# SCH_555-circuit_2025-12-22.net
KiCad netlist of a schematic drawn in EasyEDA
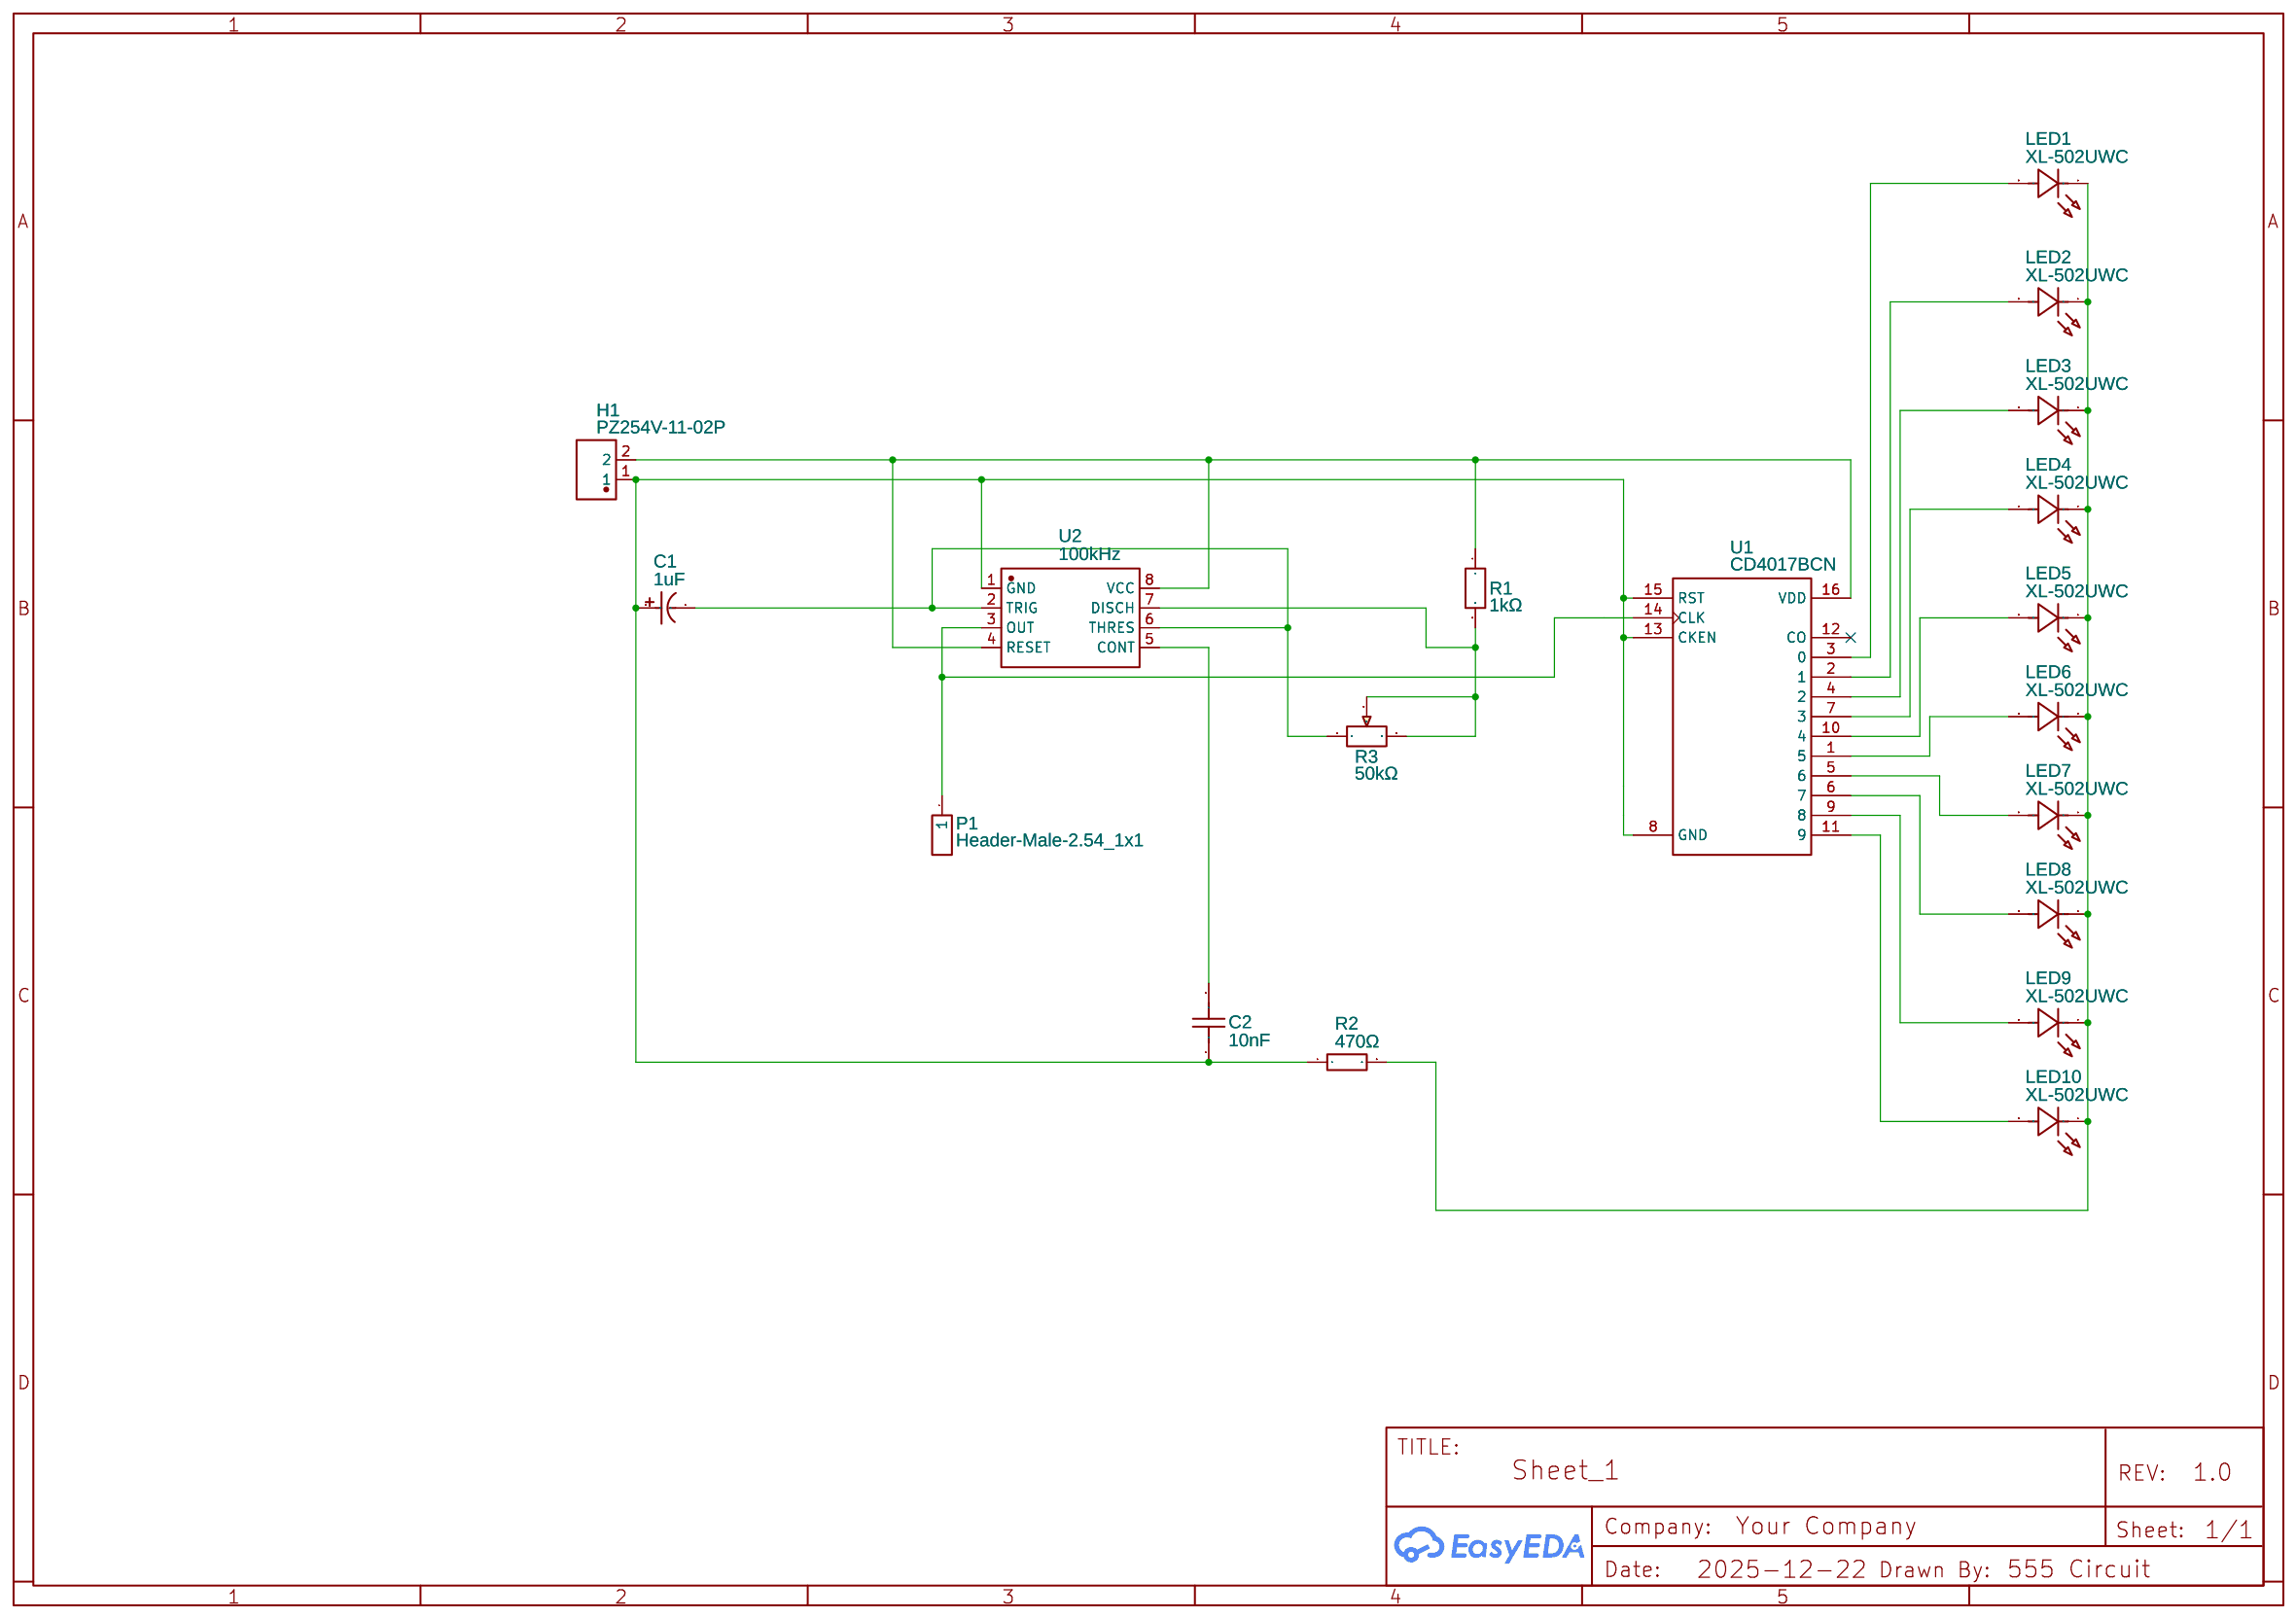
[diagram p0: schematic sheet]

(export (version "E")
  (design (tool "Eeschema 10.0.6"))
  (components
    (comp (ref "C1")
      (value "1uF")
      (fields (field (name "Manufacturer Part") "KF010M050C110A") (field (name "Manufacturer") "CapXon(丰宾)"))
      (libsource (lib "") (part "KF010M050C110A"))
    )
    (comp (ref "C2")
      (value "10nF")
      (fields (field (name "Manufacturer Part") "N09F1B103MN0B0S0N0") (field (name "Manufacturer") "STE(松田)"))
      (libsource (lib "") (part "N09F1B103MN0B0S0N0"))
    )
    (comp (ref "H1")
      (value "PZ254V-11-02P")
      (fields (field (name "Manufacturer") "XFCN(兴飞)"))
      (libsource (lib "") (part "PZ254V-11-02P"))
    )
    (comp (ref "LED1")
      (value "XL-502UWC")
      (fields (field (name "Manufacturer") "XINGLIGHT(成兴光)"))
      (libsource (lib "") (part "XL-502UWC"))
    )
    (comp (ref "LED2")
      (value "XL-502UWC")
      (fields (field (name "Manufacturer") "XINGLIGHT(成兴光)"))
      (libsource (lib "") (part "XL-502UWC"))
    )
    (comp (ref "LED3")
      (value "XL-502UWC")
      (fields (field (name "Manufacturer") "XINGLIGHT(成兴光)"))
      (libsource (lib "") (part "XL-502UWC"))
    )
    (comp (ref "LED4")
      (value "XL-502UWC")
      (fields (field (name "Manufacturer") "XINGLIGHT(成兴光)"))
      (libsource (lib "") (part "XL-502UWC"))
    )
    (comp (ref "LED5")
      (value "XL-502UWC")
      (fields (field (name "Manufacturer") "XINGLIGHT(成兴光)"))
      (libsource (lib "") (part "XL-502UWC"))
    )
    (comp (ref "LED6")
      (value "XL-502UWC")
      (fields (field (name "Manufacturer") "XINGLIGHT(成兴光)"))
      (libsource (lib "") (part "XL-502UWC"))
    )
    (comp (ref "LED7")
      (value "XL-502UWC")
      (fields (field (name "Manufacturer") "XINGLIGHT(成兴光)"))
      (libsource (lib "") (part "XL-502UWC"))
    )
    (comp (ref "LED8")
      (value "XL-502UWC")
      (fields (field (name "Manufacturer") "XINGLIGHT(成兴光)"))
      (libsource (lib "") (part "XL-502UWC"))
    )
    (comp (ref "LED9")
      (value "XL-502UWC")
      (fields (field (name "Manufacturer") "XINGLIGHT(成兴光)"))
      (libsource (lib "") (part "XL-502UWC"))
    )
    (comp (ref "LED10")
      (value "XL-502UWC")
      (fields (field (name "Manufacturer") "XINGLIGHT(成兴光)"))
      (libsource (lib "") (part "XL-502UWC"))
    )
    (comp (ref "P1")
      (value "Header-Male-2.54_1x1")
      (fields (field (name "Manufacturer Part") "2.54-1*1P针") (field (name "Manufacturer") "BOOMELE(博穆精密)"))
      (libsource (lib "") (part "Header-Male-2.54_1x1"))
    )
    (comp (ref "R1")
      (value "1kΩ")
      (fields (field (name "Manufacturer Part") "MF1/4W-1KΩ±1%T52") (field (name "Manufacturer") "华星机电"))
      (libsource (lib "") (part "MF1/4W-1KΩ±1%T52"))
    )
    (comp (ref "R2")
      (value "470Ω")
      (fields
        (field (name "Manufacturer Part") "MFR0W4F4700A50")
        (field (name "Manufacturer") "UNI-ROYAL(厚声)")
      )
      (libsource (lib "") (part "MFR0W4F4700A50"))
    )
    (comp (ref "R3")
      (value "50kΩ")
      (fields (field (name "Manufacturer Part") "3296X-1-503") (field (name "Manufacturer") "BOCHEN(博晨)"))
      (libsource (lib "") (part "3296X-1-503_C118912"))
    )
    (comp (ref "U1") (value "CD4017BCN") (libsource (lib "") (part "CD4017BCN")))
    (comp (ref "U2")
      (value "100kHz")
      (fields (field (name "Manufacturer Part") "NE555P") (field (name "Manufacturer") "TI(德州仪器)"))
      (libsource (lib "") (part "NE555P"))
    )
  )
  (nets
    (net (code "1") (name "Net-(LED1-A)") (class "Default")
      (node (ref "LED1") (pin "2") (pinfunction "A_2") (pintype "unspecified"))
      (node (ref "U1") (pin "3") (pinfunction "0_3") (pintype "output"))
    )
    (net (code "2") (name "Net-(LED1-K)") (class "Default")
      (node (ref "LED1") (pin "1") (pinfunction "K_1") (pintype "unspecified"))
      (node (ref "LED10") (pin "1") (pinfunction "K_1") (pintype "unspecified"))
      (node (ref "LED2") (pin "1") (pinfunction "K_1") (pintype "unspecified"))
      (node (ref "LED3") (pin "1") (pinfunction "K_1") (pintype "unspecified"))
      (node (ref "LED4") (pin "1") (pinfunction "K_1") (pintype "unspecified"))
      (node (ref "LED5") (pin "1") (pinfunction "K_1") (pintype "unspecified"))
      (node (ref "LED6") (pin "1") (pinfunction "K_1") (pintype "unspecified"))
      (node (ref "LED7") (pin "1") (pinfunction "K_1") (pintype "unspecified"))
      (node (ref "LED8") (pin "1") (pinfunction "K_1") (pintype "unspecified"))
      (node (ref "LED9") (pin "1") (pinfunction "K_1") (pintype "unspecified"))
      (node (ref "R2") (pin "2") (pinfunction "2_2") (pintype "input"))
    )
    (net (code "3") (name "Net-(LED2-A)") (class "Default")
      (node (ref "LED2") (pin "2") (pinfunction "A_2") (pintype "unspecified"))
      (node (ref "U1") (pin "2") (pinfunction "1_2") (pintype "output"))
    )
    (net (code "4") (name "Net-(LED3-A)") (class "Default")
      (node (ref "LED3") (pin "2") (pinfunction "A_2") (pintype "unspecified"))
      (node (ref "U1") (pin "4") (pinfunction "2_4") (pintype "output"))
    )
    (net (code "5") (name "Net-(LED4-A)") (class "Default")
      (node (ref "LED4") (pin "2") (pinfunction "A_2") (pintype "unspecified"))
      (node (ref "U1") (pin "7") (pinfunction "3_7") (pintype "output"))
    )
    (net (code "6") (name "Net-(LED5-A)") (class "Default")
      (node (ref "LED5") (pin "2") (pinfunction "A_2") (pintype "unspecified"))
      (node (ref "U1") (pin "10") (pinfunction "4_10") (pintype "output"))
    )
    (net (code "7") (name "Net-(LED6-A)") (class "Default")
      (node (ref "LED6") (pin "2") (pinfunction "A_2") (pintype "unspecified"))
      (node (ref "U1") (pin "1") (pinfunction "5_1") (pintype "output"))
    )
    (net (code "8") (name "Net-(LED7-A)") (class "Default")
      (node (ref "LED7") (pin "2") (pinfunction "A_2") (pintype "unspecified"))
      (node (ref "U1") (pin "5") (pinfunction "6_5") (pintype "output"))
    )
    (net (code "9") (name "Net-(LED8-A)") (class "Default")
      (node (ref "LED8") (pin "2") (pinfunction "A_2") (pintype "unspecified"))
      (node (ref "U1") (pin "6") (pinfunction "7_6") (pintype "output"))
    )
    (net (code "10") (name "Net-(LED9-A)") (class "Default")
      (node (ref "LED9") (pin "2") (pinfunction "A_2") (pintype "unspecified"))
      (node (ref "U1") (pin "9") (pinfunction "8_9") (pintype "output"))
    )
    (net (code "11") (name "Net-(LED10-A)") (class "Default")
      (node (ref "LED10") (pin "2") (pinfunction "A_2") (pintype "unspecified"))
      (node (ref "U1") (pin "11") (pinfunction "9_11") (pintype "output"))
    )
    (net (code "12") (name "Net-(U1-CKEN)") (class "Default")
      (node (ref "C1") (pin "1") (pinfunction "1_1") (pintype "input"))
      (node (ref "C2") (pin "1") (pinfunction "1_1") (pintype "unspecified"))
      (node (ref "H1") (pin "1") (pinfunction "1_1") (pintype "unspecified"))
      (node (ref "R2") (pin "1") (pinfunction "1_1") (pintype "input"))
      (node (ref "U1") (pin "13") (pinfunction "CKEN_13") (pintype "unspecified"))
      (node (ref "U1") (pin "15") (pinfunction "RST_15") (pintype "unspecified"))
      (node (ref "U1") (pin "8") (pinfunction "GND_8") (pintype "passive"))
      (node (ref "U2") (pin "1") (pinfunction "GND_1") (pintype "unspecified"))
    )
    (net (code "13") (name "Net-(U1-CLK)") (class "Default")
      (node (ref "P1") (pin "1") (pinfunction "1_1") (pintype "input"))
      (node (ref "U1") (pin "14") (pinfunction "CLK_14") (pintype "unspecified"))
      (node (ref "U2") (pin "3") (pinfunction "OUT_3") (pintype "unspecified"))
    )
    (net (code "14") (name "Net-(U1-VDD)") (class "Default")
      (node (ref "H1") (pin "2") (pinfunction "2_2") (pintype "unspecified"))
      (node (ref "R1") (pin "1") (pinfunction "1_1") (pintype "unspecified"))
      (node (ref "U1") (pin "16") (pinfunction "VDD_16") (pintype "passive"))
      (node (ref "U2") (pin "4") (pinfunction "RESET_4") (pintype "unspecified"))
      (node (ref "U2") (pin "8") (pinfunction "VCC_8") (pintype "unspecified"))
    )
    (net (code "15") (name "Net-(U2-CONT)") (class "Default")
      (node (ref "C2") (pin "2") (pinfunction "2_2") (pintype "unspecified"))
      (node (ref "U2") (pin "5") (pinfunction "CONT_5") (pintype "unspecified"))
    )
    (net (code "16") (name "Net-(U2-DISCH)") (class "Default")
      (node (ref "R1") (pin "2") (pinfunction "2_2") (pintype "unspecified"))
      (node (ref "R3") (pin "2") (pinfunction "2_2") (pintype "input"))
      (node (ref "R3") (pin "3") (pinfunction "3_3") (pintype "input"))
      (node (ref "U2") (pin "7") (pinfunction "DISCH_7") (pintype "unspecified"))
    )
    (net (code "17") (name "Net-(U2-THRES)") (class "Default")
      (node (ref "C1") (pin "2") (pinfunction "2_2") (pintype "input"))
      (node (ref "R3") (pin "1") (pinfunction "1_1") (pintype "input"))
      (node (ref "U2") (pin "2") (pinfunction "TRIG_2") (pintype "unspecified"))
      (node (ref "U2") (pin "6") (pinfunction "THRES_6") (pintype "unspecified"))
    )
    (net (code "18") (name "unconnected-(U1-CO-Pad12)") (class "Default")
      (node (ref "U1") (pin "12") (pinfunction "CO_12") (pintype "output+no_connect"))
    )
  )
)
